# Brake_Light_Flasher.net
KiCad netlist of a schematic drawn in Altium Designer
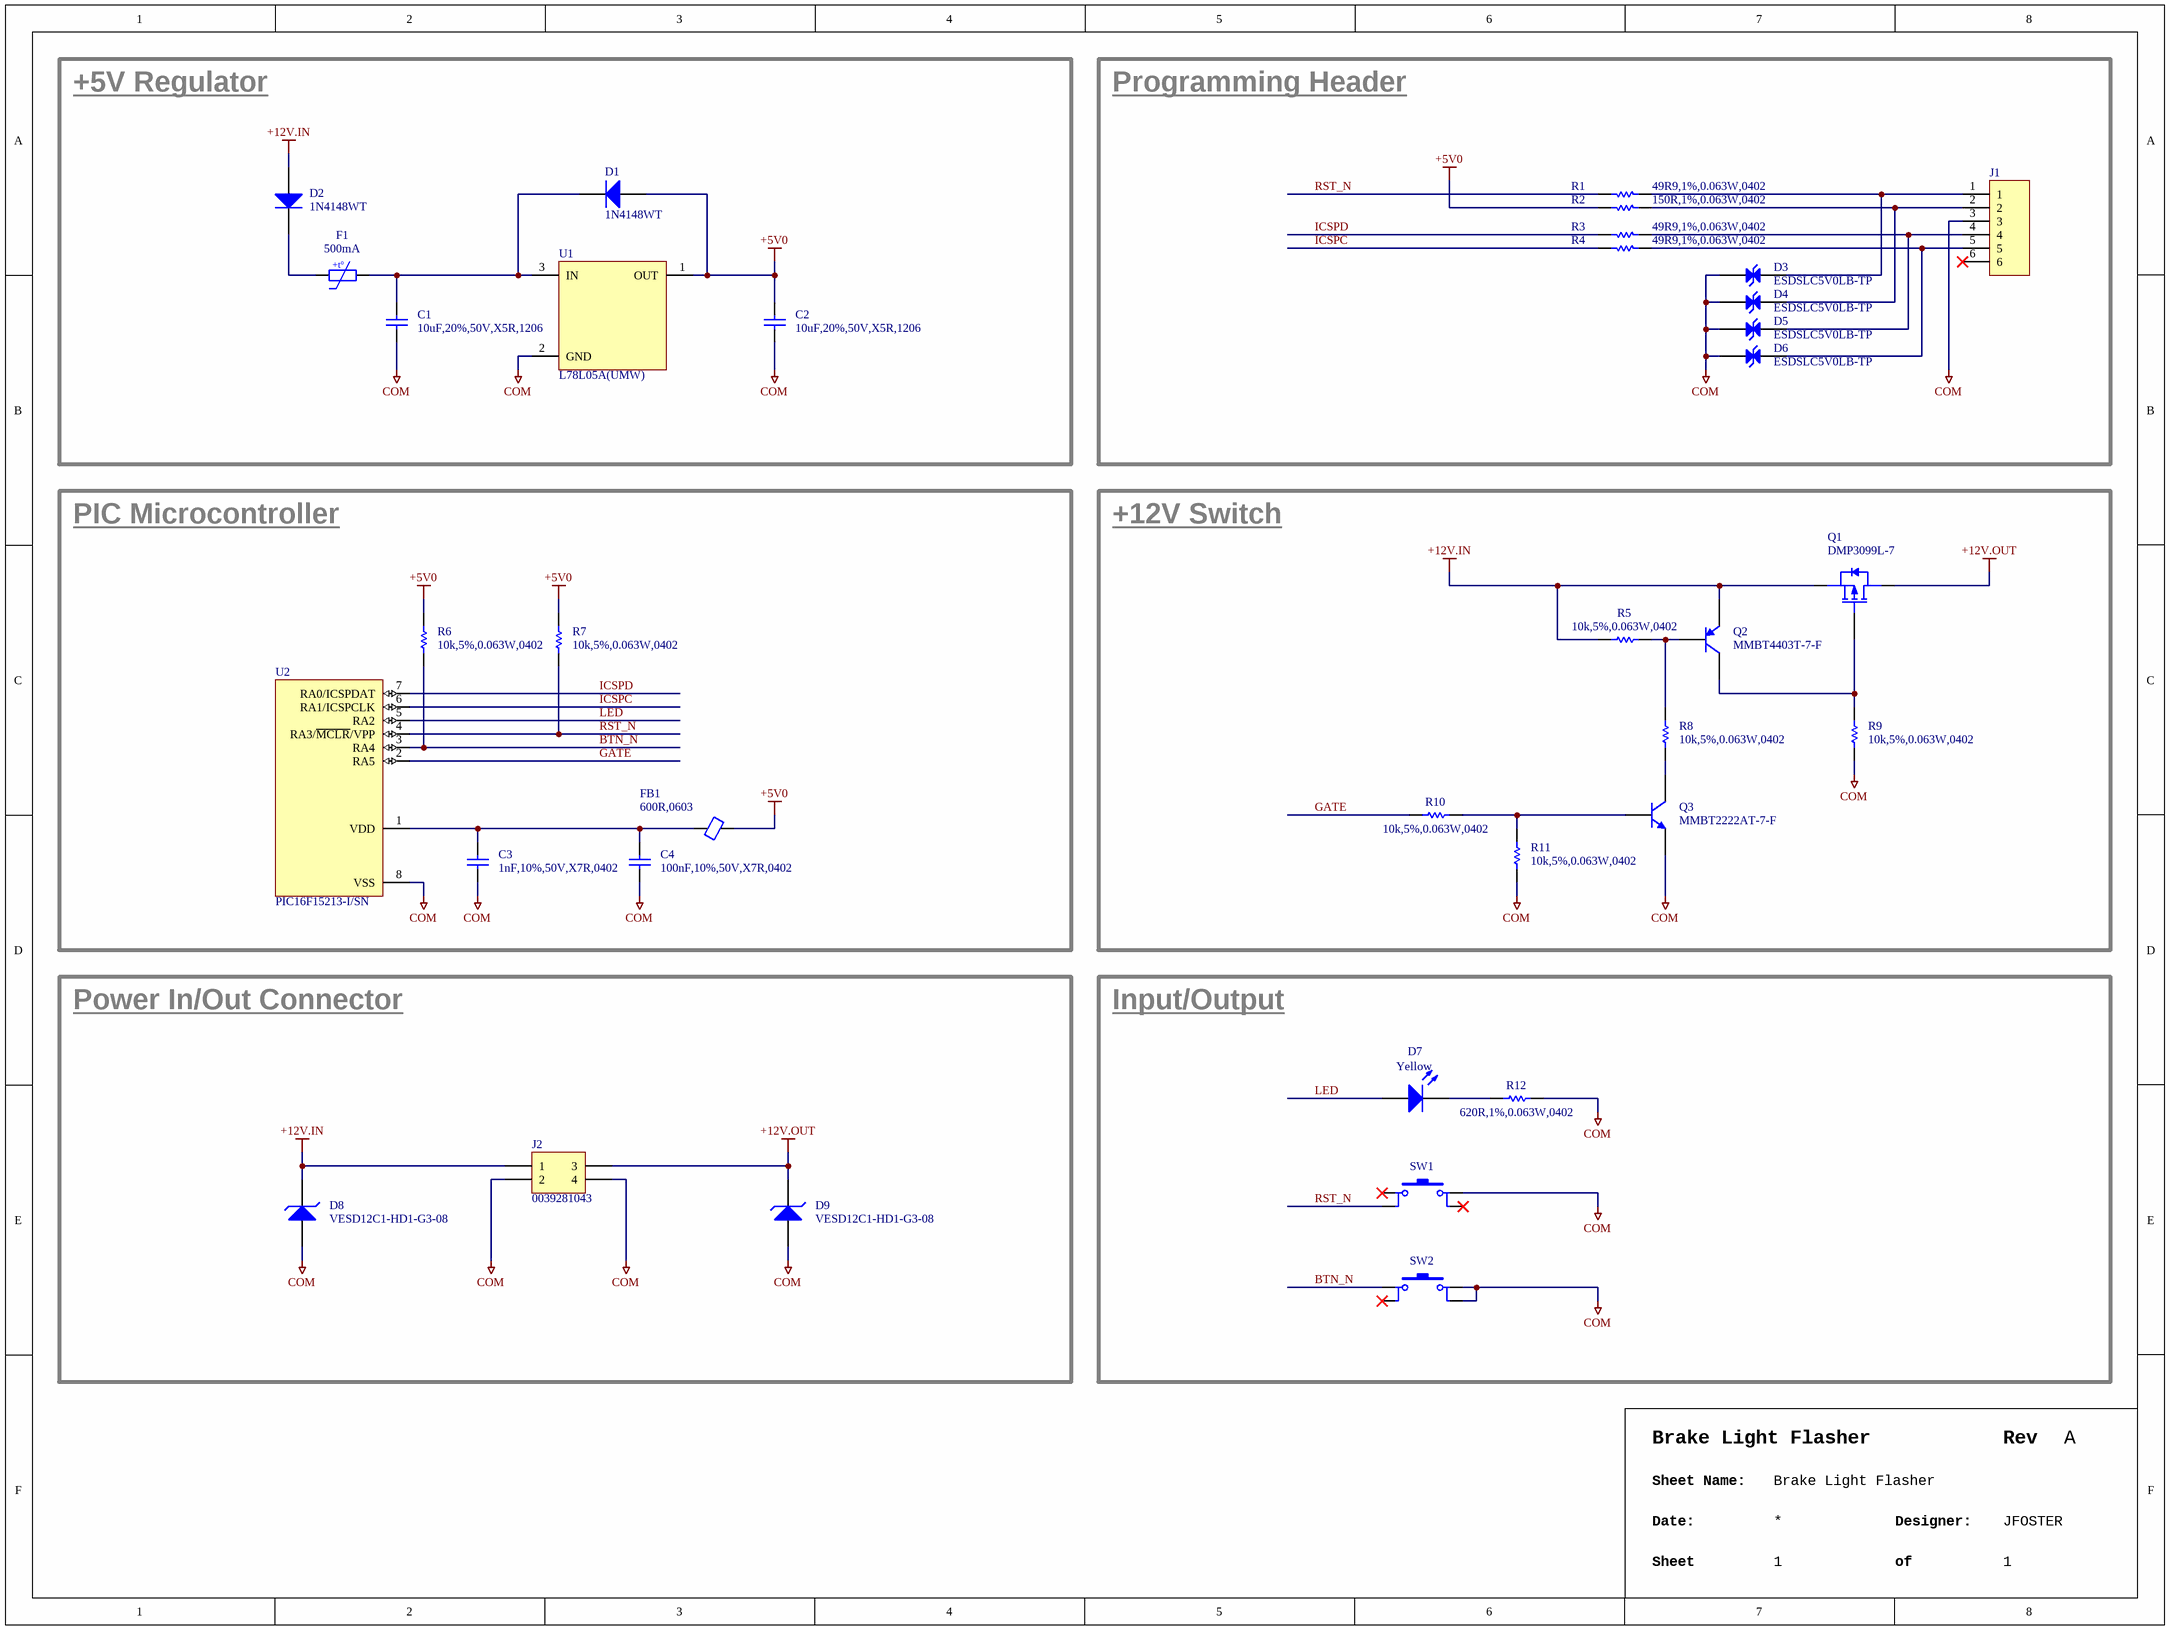
[diagram p0: Brake Light Flasher.SchDoc]

(export (version "E")
  (design (tool "Eeschema 10.0.6"))
  (components
    (comp (ref "C1")
      (value "10uF,20%,50V,X5R,1206")
      (footprint "CAPC3216X16N")
      (description "10ï¿½F ï¿½20% 50V Ceramic Capacitor X5R 1206 (3216 Metric)")
      (fields
        (field (name "MANUFACTURER 1 PART NUMBER") "CL31A106MBHNNNE")
        (field (name "VENDOR 1 PART NUMBER") "1276-6736-1-ND")
        (field (name "CREATEDBY") "Judd Foster")
      )
      (libsource (lib "Component Library") (part "CAP,Cer,10uF,50VDC,X5R,1206"))
    )
    (comp (ref "C2")
      (value "10uF,20%,50V,X5R,1206")
      (footprint "CAPC3216X16N")
      (description "10ï¿½F ï¿½20% 50V Ceramic Capacitor X5R 1206 (3216 Metric)")
      (fields
        (field (name "MANUFACTURER 1 PART NUMBER") "CL31A106MBHNNNE")
        (field (name "VENDOR 1 PART NUMBER") "1276-6736-1-ND")
        (field (name "CREATEDBY") "Judd Foster")
      )
      (libsource (lib "Component Library") (part "CAP,Cer,10uF,50VDC,X5R,1206"))
    )
    (comp (ref "C3")
      (value "1nF,10%,50V,X7R,0402")
      (footprint "CAPC1005X06N")
      (description "1000pF ï¿½10% 50V Ceramic Capacitor X7R 0402 (1005 Metric)")
      (fields
        (field (name "MANUFACTURER 1 PART NUMBER") "GCM155R71H102KA37D")
        (field (name "VENDOR 1 PART NUMBER") "490-4761-1-ND")
        (field (name "CREATEDBY") "Judd Foster")
      )
      (libsource (lib "Component Library") (part "CAP,NPOL"))
    )
    (comp (ref "C4")
      (value "100nF,10%,50V,X7R,0402")
      (footprint "CAPC1005X06N")
      (description "50V 100nF X7R Â±10% 0402 Ceramic Capacitors ROHS")
      (fields
        (field (name "MANUFACTURER 1 PART NUMBER") "GRM155R71H104KE14D")
        (field (name "VENDOR 1 PART NUMBER") "C77020")
        (field (name "CREATEDBY") "Judd Foster")
      )
      (libsource (lib "Component Library") (part "CAP,NPOL"))
    )
    (comp (ref "D1")
      (value "1N4148WT")
      (footprint "ONSEMI_PKG_SOD-523F")
      (description "Diode 75 V 200mA Surface Mount SOD-523F")
      (fields (field (name "VENDOR 1 PART NUMBER") "1N4148WTCT-ND") (field (name "CREATEDBY") "Judd Foster"))
      (libsource (lib "Component Library") (part "DIODE,Gen,75V,150mA,SOD523F"))
    )
    (comp (ref "D2")
      (value "1N4148WT")
      (footprint "ONSEMI_PKG_SOD-523F")
      (description "Diode 75 V 200mA Surface Mount SOD-523F")
      (fields (field (name "VENDOR 1 PART NUMBER") "1N4148WTCT-ND") (field (name "CREATEDBY") "Judd Foster"))
      (libsource (lib "Component Library") (part "DIODE,Gen,75V,150mA,SOD523F"))
    )
    (comp (ref "D3")
      (value "ESDSLC5V0LB-TP")
      (footprint "MICROCOMMERCIAL_DFN1006-2_NPOL")
      (description "20V Clamp 4A (8/20ï¿½s) Ipp Tvs Diode Surface Mount 2-DFN1006")
      (fields
        (field (name "VENDOR 1 PART NUMBER") "ESDSLC5V0LB-TPMSCT-ND")
        (field (name "CREATEDBY") "Judd Foster")
      )
      (libsource (lib "Component Library") (part "DIODE,TVS,5.0V,SOD882"))
    )
    (comp (ref "D4")
      (value "ESDSLC5V0LB-TP")
      (footprint "MICROCOMMERCIAL_DFN1006-2_NPOL")
      (description "20V Clamp 4A (8/20ï¿½s) Ipp Tvs Diode Surface Mount 2-DFN1006")
      (fields
        (field (name "VENDOR 1 PART NUMBER") "ESDSLC5V0LB-TPMSCT-ND")
        (field (name "CREATEDBY") "Judd Foster")
      )
      (libsource (lib "Component Library") (part "DIODE,TVS,5.0V,SOD882"))
    )
    (comp (ref "D5")
      (value "ESDSLC5V0LB-TP")
      (footprint "MICROCOMMERCIAL_DFN1006-2_NPOL")
      (description "20V Clamp 4A (8/20ï¿½s) Ipp Tvs Diode Surface Mount 2-DFN1006")
      (fields
        (field (name "VENDOR 1 PART NUMBER") "ESDSLC5V0LB-TPMSCT-ND")
        (field (name "CREATEDBY") "Judd Foster")
      )
      (libsource (lib "Component Library") (part "DIODE,TVS,5.0V,SOD882"))
    )
    (comp (ref "D6")
      (value "ESDSLC5V0LB-TP")
      (footprint "MICROCOMMERCIAL_DFN1006-2_NPOL")
      (description "20V Clamp 4A (8/20ï¿½s) Ipp Tvs Diode Surface Mount 2-DFN1006")
      (fields
        (field (name "VENDOR 1 PART NUMBER") "ESDSLC5V0LB-TPMSCT-ND")
        (field (name "CREATEDBY") "Judd Foster")
      )
      (libsource (lib "Component Library") (part "DIODE,TVS,5.0V,SOD882"))
    )
    (comp (ref "D7")
      (value "Yellow")
      (footprint "LITE-ON_LTST-C190KSKT")
      (description "Yellow 591nm LED Indication - Discrete 2.1V 0603 (1608 Metric)")
      (fields
        (field (name "MANUFACTURER 1 PART NUMBER") "LTST-C190KSKT")
        (field (name "VENDOR 1 PART NUMBER") "160-1437-1-ND")
        (field (name "CREATEDBY") "Judd Foster")
      )
      (libsource (lib "Component Library") (part "LED,Yellow,SMD,0603"))
    )
    (comp (ref "D8")
      (value "VESD12C1-HD1-G3-08")
      (footprint "VISHAY_PKG_DFN1006-2A")
      (description "Transient Voltage Suppression Diodes - TVS ESD 12V UNI")
      (fields
        (field (name "VENDOR 1 PART NUMBER") "78-VESD12C1-HD1-G308")
        (field (name "CREATEDBY") "Judd Foster")
      )
      (libsource (lib "Component Library") (part "DIODE,ESD,12V,DFN1006-2A"))
    )
    (comp (ref "D9")
      (value "VESD12C1-HD1-G3-08")
      (footprint "VISHAY_PKG_DFN1006-2A")
      (description "Transient Voltage Suppression Diodes - TVS ESD 12V UNI")
      (fields
        (field (name "VENDOR 1 PART NUMBER") "78-VESD12C1-HD1-G308")
        (field (name "CREATEDBY") "Judd Foster")
      )
      (libsource (lib "Component Library") (part "DIODE,ESD,12V,DFN1006-2A"))
    )
    (comp (ref "F1")
      (value "500mA")
      (footprint "BELFUSE_CHIP1812")
      (description "Polymeric PTC Resettable Fuse 30V 500 mA Ih Surface Mount 1812 (4532 Metric), Concave")
      (fields
        (field (name "MANUFACTURER 1 PART NUMBER") "0ZCG0050AF2C")
        (field (name "VENDOR 1 PART NUMBER") "507-1762-1-ND")
        (field (name "CREATEDBY") "Judd Foster")
      )
      (libsource (lib "Component Library") (part "PTC,30V,500mA,1812"))
    )
    (comp (ref "FB1")
      (value "600R,0603")
      (footprint "INDC_0603")
      (description "500mÎ© Â±25% 600Î©@100MHz 0603 Ferrite Beads and Chips ROHS")
      (fields
        (field (name "MANUFACTURER 1 PART NUMBER") "FCM1608KF-601T03")
        (field (name "VENDOR 1 PART NUMBER") "C141723")
        (field (name "CREATEDBY") "Judd Foster")
      )
      (libsource (lib "Component Library") (part "FERRITE"))
    )
    (comp (ref "J1")
      (value "Term,Header,6 Pin,Top,2.54mm")
      (footprint "WURTH_61300611121")
      (description "Connector Header Through Hole 6 position 0.100\" (2.54mm)")
      (fields
        (field (name "MANUFACTURER 1 PART NUMBER") "61300611121")
        (field (name "VENDOR 1 PART NUMBER") "732-5319-ND")
        (field (name "CREATEDBY") "Judd Foster")
      )
      (libsource (lib "Component Library") (part "Term,Header,6 Pin,Top,2.54mm"))
    )
    (comp (ref "J2")
      (value "0039281043")
      (footprint "MOLEX_0039281043")
      (description "Connector Header Through Hole 4 position 0.165\" (4.20mm)")
      (fields (field (name "VENDOR 1 PART NUMBER") "WM3801-ND") (field (name "CREATEDBY") "Judd Foster"))
      (libsource (lib "Component Library") (part "CONN,Mini-Fit-Jr,Hdr,2x2,Pos,Vert,Thru"))
    )
    (comp (ref "Q1")
      (value "DMP3099L-7")
      (footprint "DIODES_SOT23")
      (description "P-Channel 30 V 3.8A (Ta) 1.08W (Ta) Surface Mount SOT-23-3")
      (fields
        (field (name "VENDOR 1 PART NUMBER") "DMP3099L-7DICT-ND")
        (field (name "CREATEDBY") "Judd Foster")
      )
      (libsource (lib "Component Library") (part "MOSFET,P Ch,30V,3.8A"))
    )
    (comp (ref "Q2")
      (value "MMBT4403T-7-F")
      (footprint "DIODES_SOT523")
      (description "Bipolar (BJT) Transistor PNP 40 V 600 mA 200MHz 150 mW Surface Mount SOT-523")
      (fields
        (field (name "VENDOR 1 PART NUMBER") "MMBT4403T-FDICT-ND")
        (field (name "CREATEDBY") "Judd Foster")
      )
      (libsource (lib "Component Library") (part "Trans,PNP,40V,600mA,SOT523"))
    )
    (comp (ref "Q3")
      (value "MMBT2222AT-7-F")
      (footprint "SOTFL50P160X90-3N")
      (description "Bipolar (BJT) Transistor NPN 40 V 600 mA 300MHz 150 mW Surface Mount SOT-523")
      (fields
        (field (name "VENDOR 1 PART NUMBER") "MMBT2222AT-FDICT-ND")
        (field (name "CREATEDBY") "Judd Foster")
      )
      (libsource (lib "Component Library") (part "Trans,NPN,40V,600mA,SOT523"))
    )
    (comp (ref "R1")
      (value "49R9,1%,0.063W,0402")
      (footprint "RESC1005X04N")
      (description "49.9 Ohms Â±1% 0.063W, 1/16W Chip Resistor 0402 (1005 Metric) Moisture Resistant Thick Film")
      (fields
        (field (name "MANUFACTURER 1 PART NUMBER") "RC0402FR-0749R9L")
        (field (name "VENDOR 1 PART NUMBER") "311-49.9LRCT-ND")
        (field (name "CREATEDBY") "Judd Foster")
      )
      (libsource (lib "Component Library") (part "RES,49R9,1%,0.063W,0402"))
    )
    (comp (ref "R2")
      (value "150R,1%,0.063W,0402")
      (footprint "RESC1005X04N")
      (fields
        (field (name "MANUFACTURER 1 PART NUMBER") "CRGCQ0402F150R")
        (field (name "VENDOR 1 PART NUMBER") "A129617CT-ND")
        (field (name "CREATEDBY") "Judd Foster")
      )
      (libsource (lib "Component Library") (part "RES,150R,1%,0.1W,0402"))
    )
    (comp (ref "R3")
      (value "49R9,1%,0.063W,0402")
      (footprint "RESC1005X04N")
      (description "49.9 Ohms Â±1% 0.063W, 1/16W Chip Resistor 0402 (1005 Metric) Moisture Resistant Thick Film")
      (fields
        (field (name "MANUFACTURER 1 PART NUMBER") "RC0402FR-0749R9L")
        (field (name "VENDOR 1 PART NUMBER") "311-49.9LRCT-ND")
        (field (name "CREATEDBY") "Judd Foster")
      )
      (libsource (lib "Component Library") (part "RES,49R9,1%,0.063W,0402"))
    )
    (comp (ref "R4")
      (value "49R9,1%,0.063W,0402")
      (footprint "RESC1005X04N")
      (description "49.9 Ohms Â±1% 0.063W, 1/16W Chip Resistor 0402 (1005 Metric) Moisture Resistant Thick Film")
      (fields
        (field (name "MANUFACTURER 1 PART NUMBER") "RC0402FR-0749R9L")
        (field (name "VENDOR 1 PART NUMBER") "311-49.9LRCT-ND")
        (field (name "CREATEDBY") "Judd Foster")
      )
      (libsource (lib "Component Library") (part "RES,49R9,1%,0.063W,0402"))
    )
    (comp (ref "R5")
      (value "10k,5%,0.063W,0402")
      (footprint "RESC1005X04N")
      (description "10 kOhms ï¿½5% 0.063W, 1/16W Chip Resistor 0402 (1005 Metric) Automotive AEC-Q200 Thick Film")
      (fields
        (field (name "MANUFACTURER 1 PART NUMBER") "RMCF0402JT10K0")
        (field (name "VENDOR 1 PART NUMBER") "RMCF0402JT10K0CT-ND")
        (field (name "CREATEDBY") "Judd Foster")
      )
      (libsource (lib "Component Library") (part "RES,10k,5%,0.063W,0402"))
    )
    (comp (ref "R6")
      (value "10k,5%,0.063W,0402")
      (footprint "RESC1005X04N")
      (description "10 kOhms ï¿½5% 0.063W, 1/16W Chip Resistor 0402 (1005 Metric) Automotive AEC-Q200 Thick Film")
      (fields
        (field (name "MANUFACTURER 1 PART NUMBER") "RMCF0402JT10K0")
        (field (name "VENDOR 1 PART NUMBER") "RMCF0402JT10K0CT-ND")
        (field (name "CREATEDBY") "Judd Foster")
      )
      (libsource (lib "Component Library") (part "RES,10k,5%,0.063W,0402"))
    )
    (comp (ref "R7")
      (value "10k,5%,0.063W,0402")
      (footprint "RESC1005X04N")
      (description "10 kOhms ï¿½5% 0.063W, 1/16W Chip Resistor 0402 (1005 Metric) Automotive AEC-Q200 Thick Film")
      (fields
        (field (name "MANUFACTURER 1 PART NUMBER") "RMCF0402JT10K0")
        (field (name "VENDOR 1 PART NUMBER") "RMCF0402JT10K0CT-ND")
        (field (name "CREATEDBY") "Judd Foster")
      )
      (libsource (lib "Component Library") (part "RES,10k,5%,0.063W,0402"))
    )
    (comp (ref "R8")
      (value "10k,5%,0.063W,0402")
      (footprint "RESC1005X04N")
      (description "10 kOhms ï¿½5% 0.063W, 1/16W Chip Resistor 0402 (1005 Metric) Automotive AEC-Q200 Thick Film")
      (fields
        (field (name "MANUFACTURER 1 PART NUMBER") "RMCF0402JT10K0")
        (field (name "VENDOR 1 PART NUMBER") "RMCF0402JT10K0CT-ND")
        (field (name "CREATEDBY") "Judd Foster")
      )
      (libsource (lib "Component Library") (part "RES,10k,5%,0.063W,0402"))
    )
    (comp (ref "R9")
      (value "10k,5%,0.063W,0402")
      (footprint "RESC1005X04N")
      (description "10 kOhms ï¿½5% 0.063W, 1/16W Chip Resistor 0402 (1005 Metric) Automotive AEC-Q200 Thick Film")
      (fields
        (field (name "MANUFACTURER 1 PART NUMBER") "RMCF0402JT10K0")
        (field (name "VENDOR 1 PART NUMBER") "RMCF0402JT10K0CT-ND")
        (field (name "CREATEDBY") "Judd Foster")
      )
      (libsource (lib "Component Library") (part "RES,10k,5%,0.063W,0402"))
    )
    (comp (ref "R10")
      (value "10k,5%,0.063W,0402")
      (footprint "RESC1005X04N")
      (description "10 kOhms ï¿½5% 0.063W, 1/16W Chip Resistor 0402 (1005 Metric) Automotive AEC-Q200 Thick Film")
      (fields
        (field (name "MANUFACTURER 1 PART NUMBER") "RMCF0402JT10K0")
        (field (name "VENDOR 1 PART NUMBER") "RMCF0402JT10K0CT-ND")
        (field (name "CREATEDBY") "Judd Foster")
      )
      (libsource (lib "Component Library") (part "RES,10k,5%,0.063W,0402"))
    )
    (comp (ref "R11")
      (value "10k,5%,0.063W,0402")
      (footprint "RESC1005X04N")
      (description "10 kOhms ï¿½5% 0.063W, 1/16W Chip Resistor 0402 (1005 Metric) Automotive AEC-Q200 Thick Film")
      (fields
        (field (name "MANUFACTURER 1 PART NUMBER") "RMCF0402JT10K0")
        (field (name "VENDOR 1 PART NUMBER") "RMCF0402JT10K0CT-ND")
        (field (name "CREATEDBY") "Judd Foster")
      )
      (libsource (lib "Component Library") (part "RES,10k,5%,0.063W,0402"))
    )
    (comp (ref "R12")
      (value "620R,1%,0.063W,0402")
      (footprint "RESC1005X04N")
      (description "620 Ohms Â±1% 0.063W, 1/16W Chip Resistor 0402 (1005 Metric) Thin Film")
      (fields
        (field (name "MANUFACTURER 1 PART NUMBER") "RT0402FRE07620RL")
        (field (name "VENDOR 1 PART NUMBER") "13-RT0402FRE07620RLCT-ND")
        (field (name "CREATEDBY") "Judd Foster")
      )
      (libsource (lib "Component Library") (part "RES,620R,1%,0.063W,0402"))
    )
    (comp (ref "SW1")
      (value "PTS525SM15SMTR2 LFS")
      (footprint "C&K_PTS525SM15SMTR2 LFS")
      (description "Tactile Switch SPST-NO Top Actuated Surface Mount")
      (fields (field (name "VENDOR 1 PART NUMBER") "CKN9104CT-ND") (field (name "CREATEDBY") "Judd Foster"))
      (libsource (lib "Component Library") (part "Switch,Tactile,SPST-NO,SMD,H1.5"))
    )
    (comp (ref "SW2")
      (value "PTS525SM15SMTR2 LFS")
      (footprint "C&K_PTS525SM15SMTR2 LFS")
      (description "Tactile Switch SPST-NO Top Actuated Surface Mount")
      (fields (field (name "VENDOR 1 PART NUMBER") "CKN9104CT-ND") (field (name "CREATEDBY") "Judd Foster"))
      (libsource (lib "Component Library") (part "Switch,Tactile,SPST-NO,SMD,H1.5"))
    )
    (comp (ref "U1")
      (value "L78L05A(UMW)")
      (footprint "UMW_PKG_SOT-89-3")
      (description "Linear Voltage Regulator IC Positive Fixed 1 Output 100mA SO-8")
      (fields (field (name "VENDOR 1 PART NUMBER") "C2681223") (field (name "CREATEDBY") "Judd Foster"))
      (libsource (lib "Component Library") (part "L78L05A(UMW)"))
    )
    (comp (ref "U2")
      (value "PIC16F15213-I/SN")
      (footprint "MICROCHIP_PKG_SOIC-8(C04-2057-SN)")
      (fields
        (field (name "VENDOR 1 PART NUMBER") "150-PIC16F15213-I/SN-ND")
        (field (name "CREATEDBY") "Judd Foster")
      )
      (libsource (lib "Component Library") (part "PIC16F15213-I_SN"))
    )
  )
  (nets
    (net (code "1") (name "+5V0") (class "Default")
      (node (ref "C2") (pin "2") (pinfunction "2_2") (pintype "passive"))
      (node (ref "D1") (pin "2") (pinfunction "A_2") (pintype "passive"))
      (node (ref "FB1") (pin "2") (pinfunction "2_2") (pintype "passive"))
      (node (ref "R2") (pin "1") (pinfunction "1_1") (pintype "passive"))
      (node (ref "R6") (pin "2") (pinfunction "2_2") (pintype "passive"))
      (node (ref "R7") (pin "2") (pinfunction "2_2") (pintype "passive"))
      (node (ref "U1") (pin "1") (pinfunction "OUT_1") (pintype "passive"))
    )
    (net (code "2") (name "+12V.IN") (class "Default")
      (node (ref "D2") (pin "2") (pinfunction "A_2") (pintype "passive"))
      (node (ref "D8") (pin "2") (pinfunction "K_2") (pintype "passive"))
      (node (ref "J2") (pin "1") (pinfunction "1_1") (pintype "power_in"))
      (node (ref "Q1") (pin "2") (pinfunction "S_2") (pintype "passive"))
      (node (ref "Q2") (pin "2") (pinfunction "E_2") (pintype "passive"))
      (node (ref "R5") (pin "2") (pinfunction "2_2") (pintype "passive"))
    )
    (net (code "3") (name "+12V.OUT") (class "Default")
      (node (ref "D9") (pin "2") (pinfunction "K_2") (pintype "passive"))
      (node (ref "J2") (pin "3") (pinfunction "3_3") (pintype "power_in"))
      (node (ref "Q1") (pin "3") (pinfunction "D_3") (pintype "passive"))
    )
    (net (code "4") (name "/BTN_N") (class "Default")
      (node (ref "R6") (pin "1") (pinfunction "1_1") (pintype "passive"))
      (node (ref "SW2") (pin "1") (pinfunction "1_1") (pintype "passive"))
      (node (ref "U2") (pin "3") (pinfunction "RA4_3") (pintype "bidirectional"))
    )
    (net (code "5") (name "/GATE") (class "Default")
      (node (ref "R10") (pin "2") (pinfunction "2_2") (pintype "passive"))
      (node (ref "U2") (pin "2") (pinfunction "RA5_2") (pintype "bidirectional"))
    )
    (net (code "6") (name "/ICSPC") (class "Default")
      (node (ref "R4") (pin "2") (pinfunction "2_2") (pintype "passive"))
      (node (ref "U2") (pin "6") (pinfunction "RA1/ICSPCLK_6") (pintype "bidirectional"))
    )
    (net (code "7") (name "/ICSPD") (class "Default")
      (node (ref "R3") (pin "2") (pinfunction "2_2") (pintype "passive"))
      (node (ref "U2") (pin "7") (pinfunction "RA0/ICSPDAT_7") (pintype "bidirectional"))
    )
    (net (code "8") (name "/LED") (class "Default")
      (node (ref "D7") (pin "A") (pinfunction "A_A") (pintype "passive"))
      (node (ref "U2") (pin "5") (pinfunction "RA2_5") (pintype "bidirectional"))
    )
    (net (code "9") (name "/RST_N") (class "Default")
      (node (ref "R1") (pin "2") (pinfunction "2_2") (pintype "passive"))
      (node (ref "R7") (pin "1") (pinfunction "1_1") (pintype "passive"))
      (node (ref "SW1") (pin "2") (pinfunction "2_2") (pintype "passive"))
      (node (ref "U2") (pin "4") (pinfunction "RA3/~{MCLR}/VPP_4") (pintype "bidirectional"))
    )
    (net (code "10") (name "COM") (class "Default")
      (node (ref "C1") (pin "1") (pinfunction "1_1") (pintype "passive"))
      (node (ref "C2") (pin "1") (pinfunction "1_1") (pintype "passive"))
      (node (ref "C3") (pin "1") (pinfunction "1_1") (pintype "passive"))
      (node (ref "C4") (pin "1") (pinfunction "1_1") (pintype "passive"))
      (node (ref "D3") (pin "1") (pinfunction "K_1") (pintype "passive"))
      (node (ref "D4") (pin "1") (pinfunction "K_1") (pintype "passive"))
      (node (ref "D5") (pin "1") (pinfunction "K_1") (pintype "passive"))
      (node (ref "D6") (pin "1") (pinfunction "K_1") (pintype "passive"))
      (node (ref "D8") (pin "1") (pinfunction "A_1") (pintype "passive"))
      (node (ref "D9") (pin "1") (pinfunction "A_1") (pintype "passive"))
      (node (ref "J1") (pin "3") (pinfunction "3_3") (pintype "passive"))
      (node (ref "J2") (pin "2") (pinfunction "2_2") (pintype "power_in"))
      (node (ref "J2") (pin "4") (pinfunction "4_4") (pintype "power_in"))
      (node (ref "Q3") (pin "2") (pinfunction "E_2") (pintype "passive"))
      (node (ref "R11") (pin "1") (pinfunction "1_1") (pintype "passive"))
      (node (ref "R12") (pin "2") (pinfunction "2_2") (pintype "passive"))
      (node (ref "R9") (pin "1") (pinfunction "1_1") (pintype "passive"))
      (node (ref "SW1") (pin "3") (pinfunction "3_3") (pintype "passive"))
      (node (ref "SW2") (pin "3") (pinfunction "3_3") (pintype "passive"))
      (node (ref "SW2") (pin "4") (pinfunction "4_4") (pintype "passive"))
      (node (ref "U1") (pin "2") (pinfunction "GND_2") (pintype "passive"))
      (node (ref "U2") (pin "8") (pinfunction "VSS_8") (pintype "power_in"))
    )
    (net (code "11") (name "Net-(D1-K)") (class "Default")
      (node (ref "C1") (pin "2") (pinfunction "2_2") (pintype "passive"))
      (node (ref "D1") (pin "1") (pinfunction "K_1") (pintype "passive"))
      (node (ref "F1") (pin "2") (pinfunction "2_2") (pintype "passive"))
      (node (ref "U1") (pin "3") (pinfunction "IN_3") (pintype "passive"))
    )
    (net (code "12") (name "Net-(D2-K)") (class "Default")
      (node (ref "D2") (pin "1") (pinfunction "K_1") (pintype "passive"))
      (node (ref "F1") (pin "1") (pinfunction "1_1") (pintype "passive"))
    )
    (net (code "13") (name "Net-(D3-A)") (class "Default")
      (node (ref "D3") (pin "2") (pinfunction "A_2") (pintype "passive"))
      (node (ref "J1") (pin "1") (pinfunction "1_1") (pintype "passive"))
      (node (ref "R1") (pin "1") (pinfunction "1_1") (pintype "passive"))
    )
    (net (code "14") (name "Net-(D4-A)") (class "Default")
      (node (ref "D4") (pin "2") (pinfunction "A_2") (pintype "passive"))
      (node (ref "J1") (pin "2") (pinfunction "2_2") (pintype "passive"))
      (node (ref "R2") (pin "2") (pinfunction "2_2") (pintype "passive"))
    )
    (net (code "15") (name "Net-(D5-A)") (class "Default")
      (node (ref "D5") (pin "2") (pinfunction "A_2") (pintype "passive"))
      (node (ref "J1") (pin "4") (pinfunction "4_4") (pintype "passive"))
      (node (ref "R3") (pin "1") (pinfunction "1_1") (pintype "passive"))
    )
    (net (code "16") (name "Net-(D6-A)") (class "Default")
      (node (ref "D6") (pin "2") (pinfunction "A_2") (pintype "passive"))
      (node (ref "J1") (pin "5") (pinfunction "5_5") (pintype "passive"))
      (node (ref "R4") (pin "1") (pinfunction "1_1") (pintype "passive"))
    )
    (net (code "17") (name "Net-(D7-PadC)") (class "Default")
      (node (ref "D7") (pin "C") (pinfunction "C_C") (pintype "passive"))
      (node (ref "R12") (pin "1") (pinfunction "1_1") (pintype "passive"))
    )
    (net (code "18") (name "Net-(Q1-G)") (class "Default")
      (node (ref "Q1") (pin "1") (pinfunction "G_1") (pintype "passive"))
      (node (ref "Q2") (pin "3") (pinfunction "C_3") (pintype "passive"))
      (node (ref "R9") (pin "2") (pinfunction "2_2") (pintype "passive"))
    )
    (net (code "19") (name "Net-(Q2-B)") (class "Default")
      (node (ref "Q2") (pin "1") (pinfunction "B_1") (pintype "passive"))
      (node (ref "R5") (pin "1") (pinfunction "1_1") (pintype "passive"))
      (node (ref "R8") (pin "2") (pinfunction "2_2") (pintype "passive"))
    )
    (net (code "20") (name "Net-(Q3-B)") (class "Default")
      (node (ref "Q3") (pin "1") (pinfunction "B_1") (pintype "passive"))
      (node (ref "R10") (pin "1") (pinfunction "1_1") (pintype "passive"))
      (node (ref "R11") (pin "2") (pinfunction "2_2") (pintype "passive"))
    )
    (net (code "21") (name "Net-(Q3-C)") (class "Default")
      (node (ref "Q3") (pin "3") (pinfunction "C_3") (pintype "passive"))
      (node (ref "R8") (pin "1") (pinfunction "1_1") (pintype "passive"))
    )
    (net (code "22") (name "Net-(U2-VDD)") (class "Default")
      (node (ref "C3") (pin "2") (pinfunction "2_2") (pintype "passive"))
      (node (ref "C4") (pin "2") (pinfunction "2_2") (pintype "passive"))
      (node (ref "FB1") (pin "1") (pinfunction "1_1") (pintype "passive"))
      (node (ref "U2") (pin "1") (pinfunction "VDD_1") (pintype "power_in"))
    )
    (net (code "23") (name "unconnected-(J1-Pad6)") (class "Default")
      (node (ref "J1") (pin "6") (pinfunction "6_6") (pintype "passive+no_connect"))
    )
    (net (code "24") (name "unconnected-(SW1-Pad1)") (class "Default")
      (node (ref "SW1") (pin "1") (pinfunction "1_1") (pintype "passive+no_connect"))
    )
    (net (code "25") (name "unconnected-(SW1-Pad4)") (class "Default")
      (node (ref "SW1") (pin "4") (pinfunction "4_4") (pintype "passive+no_connect"))
    )
    (net (code "26") (name "unconnected-(SW2-Pad2)") (class "Default")
      (node (ref "SW2") (pin "2") (pinfunction "2_2") (pintype "passive+no_connect"))
    )
  )
)
